# Power.net
KiCad netlist of a schematic drawn in Altium Designer
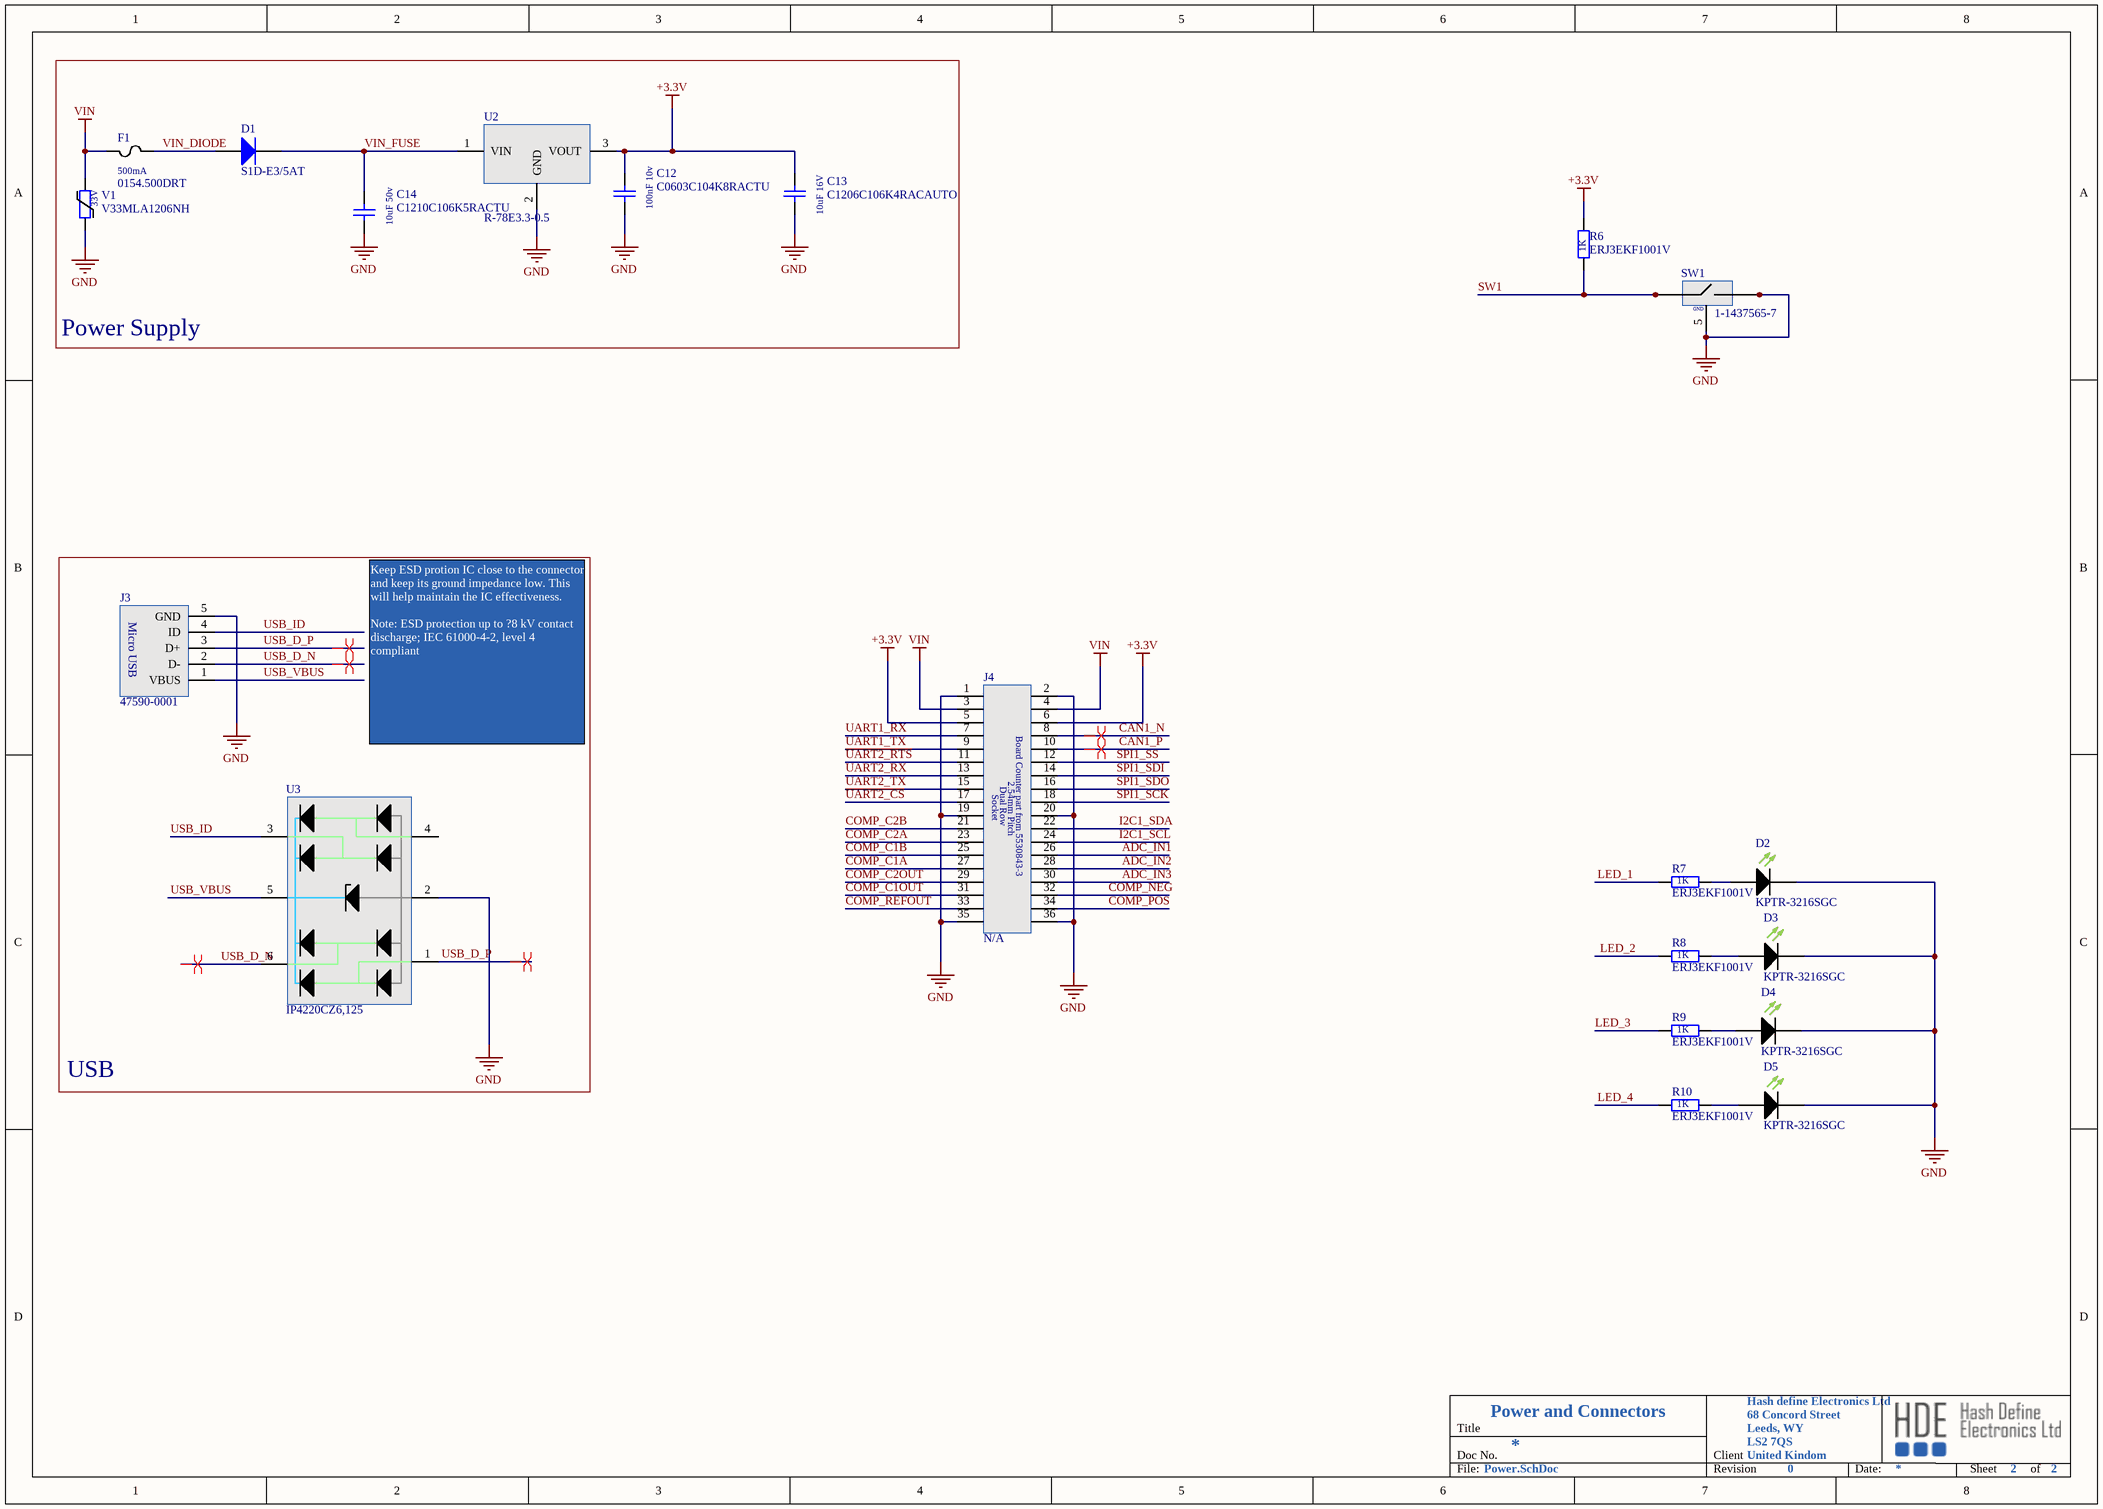
[diagram p0: Power.SchDoc]

(export (version "E")
  (design (tool "Eeschema 10.0.6"))
  (components
    (comp (ref "C12")
      (value "#NAME?")
      (footprint "CAP_0603")
      (description "100nF, 10V, 0603, -55C to 125C, X7R, 10%")
      (fields (field (name "PARTNUM") "C0603C104K8RACTU"))
      (libsource (lib "HashDefineElectronics") (part "C0603C104K8RACTU"))
    )
    (comp (ref "C13")
      (value "#NAME?")
      (footprint "CAP_1206")
      (description "10uF, 16V,  1206, -55C to 125C, X7R, 10%, Automotive")
      (fields (field (name "PARTNUM") "C1206C106K4RACAUTO"))
      (libsource (lib "HashDefineElectronics") (part "C1206C106K4RACAUTO"))
    )
    (comp (ref "C14")
      (value "#NAME?")
      (footprint "CAP_1210")
      (description "MLCC, X7R, 10uF, 50V, 1210")
      (fields (field (name "PARTNUM") "C1210C106K5RACTU"))
      (libsource (lib "HashDefineElectronics") (part "C1210C106K5RACTU"))
    )
    (comp (ref "D1")
      (value "#NAME?")
      (footprint "DO-214AC")
      (description "1A, 200V, SMD Diode")
      (fields (field (name "PARTNUM") "S1D-E3/5AT"))
      (libsource (lib "HashDefineElectronics") (part "S1D-E3/5AT"))
    )
    (comp (ref "D2")
      (value "LED")
      (footprint "LED_1206")
      (description "Green, 1206, SMD LED")
      (fields (field (name "PARTNUM") "KPTR-3216SGC"))
      (libsource (lib "HashDefineElectronics") (part "KPTR-3216SGC"))
    )
    (comp (ref "D3")
      (value "LED")
      (footprint "LED_1206")
      (description "Green, 1206, SMD LED")
      (fields (field (name "PARTNUM") "KPTR-3216SGC"))
      (libsource (lib "HashDefineElectronics") (part "KPTR-3216SGC"))
    )
    (comp (ref "D4")
      (value "LED")
      (footprint "LED_1206")
      (description "Green, 1206, SMD LED")
      (fields (field (name "PARTNUM") "KPTR-3216SGC"))
      (libsource (lib "HashDefineElectronics") (part "KPTR-3216SGC"))
    )
    (comp (ref "D5")
      (value "LED")
      (footprint "LED_1206")
      (description "Green, 1206, SMD LED")
      (fields (field (name "PARTNUM") "KPTR-3216SGC"))
      (libsource (lib "HashDefineElectronics") (part "KPTR-3216SGC"))
    )
    (comp (ref "F1")
      (value "#NAME?")
      (footprint "SMF_OMNI-BLOK")
      (description "500mA, SMD, 125v, -55C to 125C")
      (fields (field (name "PARTNUM") "0154.500DRT"))
      (libsource (lib "HashDefineElectronics") (part "0154.500DRT"))
    )
    (comp (ref "J3")
      (value "47590-0001")
      (footprint "47590-0001")
      (description "Micro USB, Top Mount")
      (fields (field (name "PARTNUM") "47590-0001"))
      (libsource (lib "HashDefineElectronics") (part "47590-0001"))
    )
    (comp (ref "J4")
      (value "N/A")
      (footprint "5530843-3_BoardEdge")
      (description "36way dual row 2.54mm socket. Board edge counter partconnector")
      (fields (field (name "PARTNUM") "N/A"))
      (libsource (lib "HashDefineElectronics") (part "5530843-3_BoardEdge"))
    )
    (comp (ref "R6")
      (value "#NAME?")
      (footprint "RES_0603")
      (description "1K, 0603, 1%, 0.1W, resistor")
      (fields (field (name "PARTNUM") "ERJ3EKF1001V"))
      (libsource (lib "") (part "ERJ3EKF1001V_1"))
    )
    (comp (ref "R7")
      (value "#NAME?")
      (footprint "RES_0603")
      (description "1K, 0603, 1%, 0.1W, resistor")
      (fields (field (name "PARTNUM") "ERJ3EKF1001V"))
      (libsource (lib "HashDefineElectronics") (part "ERJ3EKF1001V"))
    )
    (comp (ref "R8")
      (value "#NAME?")
      (footprint "RES_0603")
      (description "1K, 0603, 1%, 0.1W, resistor")
      (fields (field (name "PARTNUM") "ERJ3EKF1001V"))
      (libsource (lib "HashDefineElectronics") (part "ERJ3EKF1001V"))
    )
    (comp (ref "R9")
      (value "#NAME?")
      (footprint "RES_0603")
      (description "1K, 0603, 1%, 0.1W, resistor")
      (fields (field (name "PARTNUM") "ERJ3EKF1001V"))
      (libsource (lib "HashDefineElectronics") (part "ERJ3EKF1001V"))
    )
    (comp (ref "R10")
      (value "#NAME?")
      (footprint "RES_0603")
      (description "1K, 0603, 1%, 0.1W, resistor")
      (fields (field (name "PARTNUM") "ERJ3EKF1001V"))
      (libsource (lib "HashDefineElectronics") (part "ERJ3EKF1001V"))
    )
    (comp (ref "SW1")
      (value "1-1437565-7")
      (footprint "1-1437565-7")
      (description "TACTILE SWITCH, SPST, 0.05A, 24V")
      (fields (field (name "PARTNUM") "1-1437565-7"))
      (libsource (lib "HashDefineElectronics") (part "1-1437565-7"))
    )
    (comp (ref "U2")
      (value "#NAME?")
      (footprint "R-78E3.3-0.5")
      (description "3.3V, 500mA, DC-DC")
      (fields (field (name "PARTNUM") "R-78E3.3-0.5"))
      (libsource (lib "HashDefineElectronics") (part "R-78E3.3-0.5"))
    )
    (comp (ref "U3")
      (value "IP4220CZ6,125")
      (footprint "TSOP6")
      (description "ESD PROTECTION, DUAL USB 2.0, 6TSOP")
      (fields (field (name "PARTNUM") "IP4220CZ6,125"))
      (libsource (lib "HashDefineElectronics") (part "IP4220CZ6,125"))
    )
    (comp (ref "V1")
      (value "#NAME?")
      (footprint "1206_LittelFuse_Varistor")
      (description "33V, 1206, 180Apk, Clamp 75V")
      (fields (field (name "PARTNUM") "V33MLA1206NH"))
      (libsource (lib "HashDefineElectronics") (part "V33MLA1206NH"))
    )
  )
  (nets
    (net (code "1") (name "+3.3V") (class "Default")
      (node (ref "C12") (pin "2") (pinfunction "2_2") (pintype "passive"))
      (node (ref "C13") (pin "2") (pinfunction "2_2") (pintype "passive"))
      (node (ref "J4") (pin "5") (pinfunction "5_5") (pintype "passive"))
      (node (ref "J4") (pin "6") (pinfunction "6_6") (pintype "passive"))
      (node (ref "R6") (pin "2") (pinfunction "2_2") (pintype "passive"))
      (node (ref "U2") (pin "3") (pinfunction "VOUT_3") (pintype "power_in"))
    )
    (net (code "2") (name "/ADC_IN1") (class "Default")
      (node (ref "J4") (pin "26") (pinfunction "26_26") (pintype "passive"))
    )
    (net (code "3") (name "/ADC_IN2") (class "Default")
      (node (ref "J4") (pin "28") (pinfunction "28_28") (pintype "passive"))
    )
    (net (code "4") (name "/ADC_IN3") (class "Default")
      (node (ref "J4") (pin "30") (pinfunction "30_30") (pintype "passive"))
    )
    (net (code "5") (name "/CAN1_N") (class "Default")
      (node (ref "J4") (pin "8") (pinfunction "8_8") (pintype "passive"))
    )
    (net (code "6") (name "/CAN1_P") (class "Default")
      (node (ref "J4") (pin "10") (pinfunction "10_10") (pintype "passive"))
    )
    (net (code "7") (name "/COMP_C1A") (class "Default")
      (node (ref "J4") (pin "27") (pinfunction "27_27") (pintype "passive"))
    )
    (net (code "8") (name "/COMP_C1B") (class "Default")
      (node (ref "J4") (pin "25") (pinfunction "25_25") (pintype "passive"))
    )
    (net (code "9") (name "/COMP_C1OUT") (class "Default")
      (node (ref "J4") (pin "31") (pinfunction "31_31") (pintype "passive"))
    )
    (net (code "10") (name "/COMP_C2A") (class "Default")
      (node (ref "J4") (pin "23") (pinfunction "23_23") (pintype "passive"))
    )
    (net (code "11") (name "/COMP_C2B") (class "Default")
      (node (ref "J4") (pin "21") (pinfunction "21_21") (pintype "passive"))
    )
    (net (code "12") (name "/COMP_C2OUT") (class "Default")
      (node (ref "J4") (pin "29") (pinfunction "29_29") (pintype "passive"))
    )
    (net (code "13") (name "/COMP_NEG") (class "Default")
      (node (ref "J4") (pin "32") (pinfunction "32_32") (pintype "passive"))
    )
    (net (code "14") (name "/COMP_POS") (class "Default")
      (node (ref "J4") (pin "34") (pinfunction "34_34") (pintype "passive"))
    )
    (net (code "15") (name "/COMP_REFOUT") (class "Default")
      (node (ref "J4") (pin "33") (pinfunction "33_33") (pintype "passive"))
    )
    (net (code "16") (name "/I2C1_SCL") (class "Default")
      (node (ref "J4") (pin "24") (pinfunction "24_24") (pintype "passive"))
    )
    (net (code "17") (name "/I2C1_SDA") (class "Default")
      (node (ref "J4") (pin "22") (pinfunction "22_22") (pintype "passive"))
    )
    (net (code "18") (name "/LED_1") (class "Default")
      (node (ref "R7") (pin "1") (pinfunction "1_1") (pintype "passive"))
    )
    (net (code "19") (name "/LED_2") (class "Default")
      (node (ref "R8") (pin "1") (pinfunction "1_1") (pintype "passive"))
    )
    (net (code "20") (name "/LED_3") (class "Default")
      (node (ref "R9") (pin "1") (pinfunction "1_1") (pintype "passive"))
    )
    (net (code "21") (name "/LED_4") (class "Default")
      (node (ref "R10") (pin "1") (pinfunction "1_1") (pintype "passive"))
    )
    (net (code "22") (name "/SPI1_SCK") (class "Default")
      (node (ref "J4") (pin "18") (pinfunction "18_18") (pintype "passive"))
    )
    (net (code "23") (name "/SPI1_SDI") (class "Default")
      (node (ref "J4") (pin "14") (pinfunction "14_14") (pintype "passive"))
    )
    (net (code "24") (name "/SPI1_SDO") (class "Default")
      (node (ref "J4") (pin "16") (pinfunction "16_16") (pintype "passive"))
    )
    (net (code "25") (name "/SPI1_SS") (class "Default")
      (node (ref "J4") (pin "12") (pinfunction "12_12") (pintype "passive"))
    )
    (net (code "26") (name "/SW1") (class "Default")
      (node (ref "R6") (pin "1") (pinfunction "1_1") (pintype "passive"))
      (node (ref "SW1") (pin "1") (pinfunction "1_1") (pintype "passive"))
      (node (ref "SW1") (pin "2") (pinfunction "2_2") (pintype "passive"))
    )
    (net (code "27") (name "/UART1_RX") (class "Default")
      (node (ref "J4") (pin "7") (pinfunction "7_7") (pintype "passive"))
    )
    (net (code "28") (name "/UART1_TX") (class "Default")
      (node (ref "J4") (pin "9") (pinfunction "9_9") (pintype "passive"))
    )
    (net (code "29") (name "/UART2_RX") (class "Default")
      (node (ref "J4") (pin "13") (pinfunction "13_13") (pintype "passive"))
    )
    (net (code "30") (name "/UART2_TX") (class "Default")
      (node (ref "J4") (pin "15") (pinfunction "15_15") (pintype "passive"))
    )
    (net (code "31") (name "/USB_D_N") (class "Default")
      (node (ref "J3") (pin "2") (pinfunction "D-_2") (pintype "passive"))
      (node (ref "U3") (pin "6") (pinfunction "IO4_6") (pintype "passive"))
    )
    (net (code "32") (name "/USB_D_P") (class "Default")
      (node (ref "J3") (pin "3") (pinfunction "D+_3") (pintype "passive"))
      (node (ref "U3") (pin "1") (pinfunction "IO1_1") (pintype "passive"))
    )
    (net (code "33") (name "/USB_ID") (class "Default")
      (node (ref "J3") (pin "4") (pinfunction "ID_4") (pintype "passive"))
      (node (ref "U3") (pin "3") (pinfunction "IO2_3") (pintype "passive"))
    )
    (net (code "34") (name "/USB_VBUS") (class "Default")
      (node (ref "J3") (pin "1") (pinfunction "VBUS_1") (pintype "passive"))
      (node (ref "U3") (pin "5") (pinfunction "Vp_5") (pintype "power_in"))
    )
    (net (code "35") (name "/VIN_DIODE") (class "Default")
      (node (ref "D1") (pin "2") (pinfunction "A_2") (pintype "passive"))
      (node (ref "F1") (pin "2") (pinfunction "2_2") (pintype "passive"))
    )
    (net (code "36") (name "/VIN_FUSE") (class "Default")
      (node (ref "C14") (pin "2") (pinfunction "2_2") (pintype "passive"))
      (node (ref "D1") (pin "1") (pinfunction "K_1") (pintype "passive"))
      (node (ref "U2") (pin "1") (pinfunction "VIN_1") (pintype "power_in"))
    )
    (net (code "37") (name "/~{UART2_CS}") (class "Default")
      (node (ref "J4") (pin "17") (pinfunction "17_17") (pintype "passive"))
    )
    (net (code "38") (name "/~{UART2_RTS}") (class "Default")
      (node (ref "J4") (pin "11") (pinfunction "11_11") (pintype "passive"))
    )
    (net (code "39") (name "GND") (class "Default")
      (node (ref "C12") (pin "1") (pinfunction "1_1") (pintype "passive"))
      (node (ref "C13") (pin "1") (pinfunction "1_1") (pintype "passive"))
      (node (ref "C14") (pin "1") (pinfunction "1_1") (pintype "passive"))
      (node (ref "D2") (pin "1") (pinfunction "K_1") (pintype "passive"))
      (node (ref "D3") (pin "1") (pinfunction "K_1") (pintype "passive"))
      (node (ref "D4") (pin "1") (pinfunction "K_1") (pintype "passive"))
      (node (ref "D5") (pin "1") (pinfunction "K_1") (pintype "passive"))
      (node (ref "J3") (pin "5") (pinfunction "GND_5") (pintype "passive"))
      (node (ref "J4") (pin "1") (pinfunction "1_1") (pintype "passive"))
      (node (ref "J4") (pin "19") (pinfunction "19_19") (pintype "passive"))
      (node (ref "J4") (pin "2") (pinfunction "2_2") (pintype "passive"))
      (node (ref "J4") (pin "20") (pinfunction "20_20") (pintype "passive"))
      (node (ref "J4") (pin "35") (pinfunction "35_35") (pintype "passive"))
      (node (ref "J4") (pin "36") (pinfunction "36_36") (pintype "passive"))
      (node (ref "SW1") (pin "3") (pinfunction "3_3") (pintype "passive"))
      (node (ref "SW1") (pin "4") (pinfunction "4_4") (pintype "passive"))
      (node (ref "SW1") (pin "5") (pinfunction "GND_5") (pintype "passive"))
      (node (ref "U2") (pin "2") (pinfunction "GND_2") (pintype "power_in"))
      (node (ref "U3") (pin "2") (pinfunction "GND_2") (pintype "power_in"))
      (node (ref "V1") (pin "1") (pinfunction "1_1") (pintype "passive"))
    )
    (net (code "40") (name "Net-(D2-A)") (class "Default")
      (node (ref "D2") (pin "2") (pinfunction "A_2") (pintype "passive"))
      (node (ref "R7") (pin "2") (pinfunction "2_2") (pintype "passive"))
    )
    (net (code "41") (name "Net-(D3-A)") (class "Default")
      (node (ref "D3") (pin "2") (pinfunction "A_2") (pintype "passive"))
      (node (ref "R8") (pin "2") (pinfunction "2_2") (pintype "passive"))
    )
    (net (code "42") (name "Net-(D4-A)") (class "Default")
      (node (ref "D4") (pin "2") (pinfunction "A_2") (pintype "passive"))
      (node (ref "R9") (pin "2") (pinfunction "2_2") (pintype "passive"))
    )
    (net (code "43") (name "Net-(D5-A)") (class "Default")
      (node (ref "D5") (pin "2") (pinfunction "A_2") (pintype "passive"))
      (node (ref "R10") (pin "2") (pinfunction "2_2") (pintype "passive"))
    )
    (net (code "44") (name "VIN") (class "Default")
      (node (ref "F1") (pin "1") (pinfunction "1_1") (pintype "passive"))
      (node (ref "J4") (pin "3") (pinfunction "3_3") (pintype "passive"))
      (node (ref "J4") (pin "4") (pinfunction "4_4") (pintype "passive"))
      (node (ref "V1") (pin "2") (pinfunction "2_2") (pintype "passive"))
    )
    (net (code "45") (name "unconnected-(U3-IO3-Pad4)") (class "Default")
      (node (ref "U3") (pin "4") (pinfunction "IO3_4") (pintype "passive"))
    )
  )
)
